# Koala_Bear.net
KiCad netlist of a schematic drawn in EAGLE
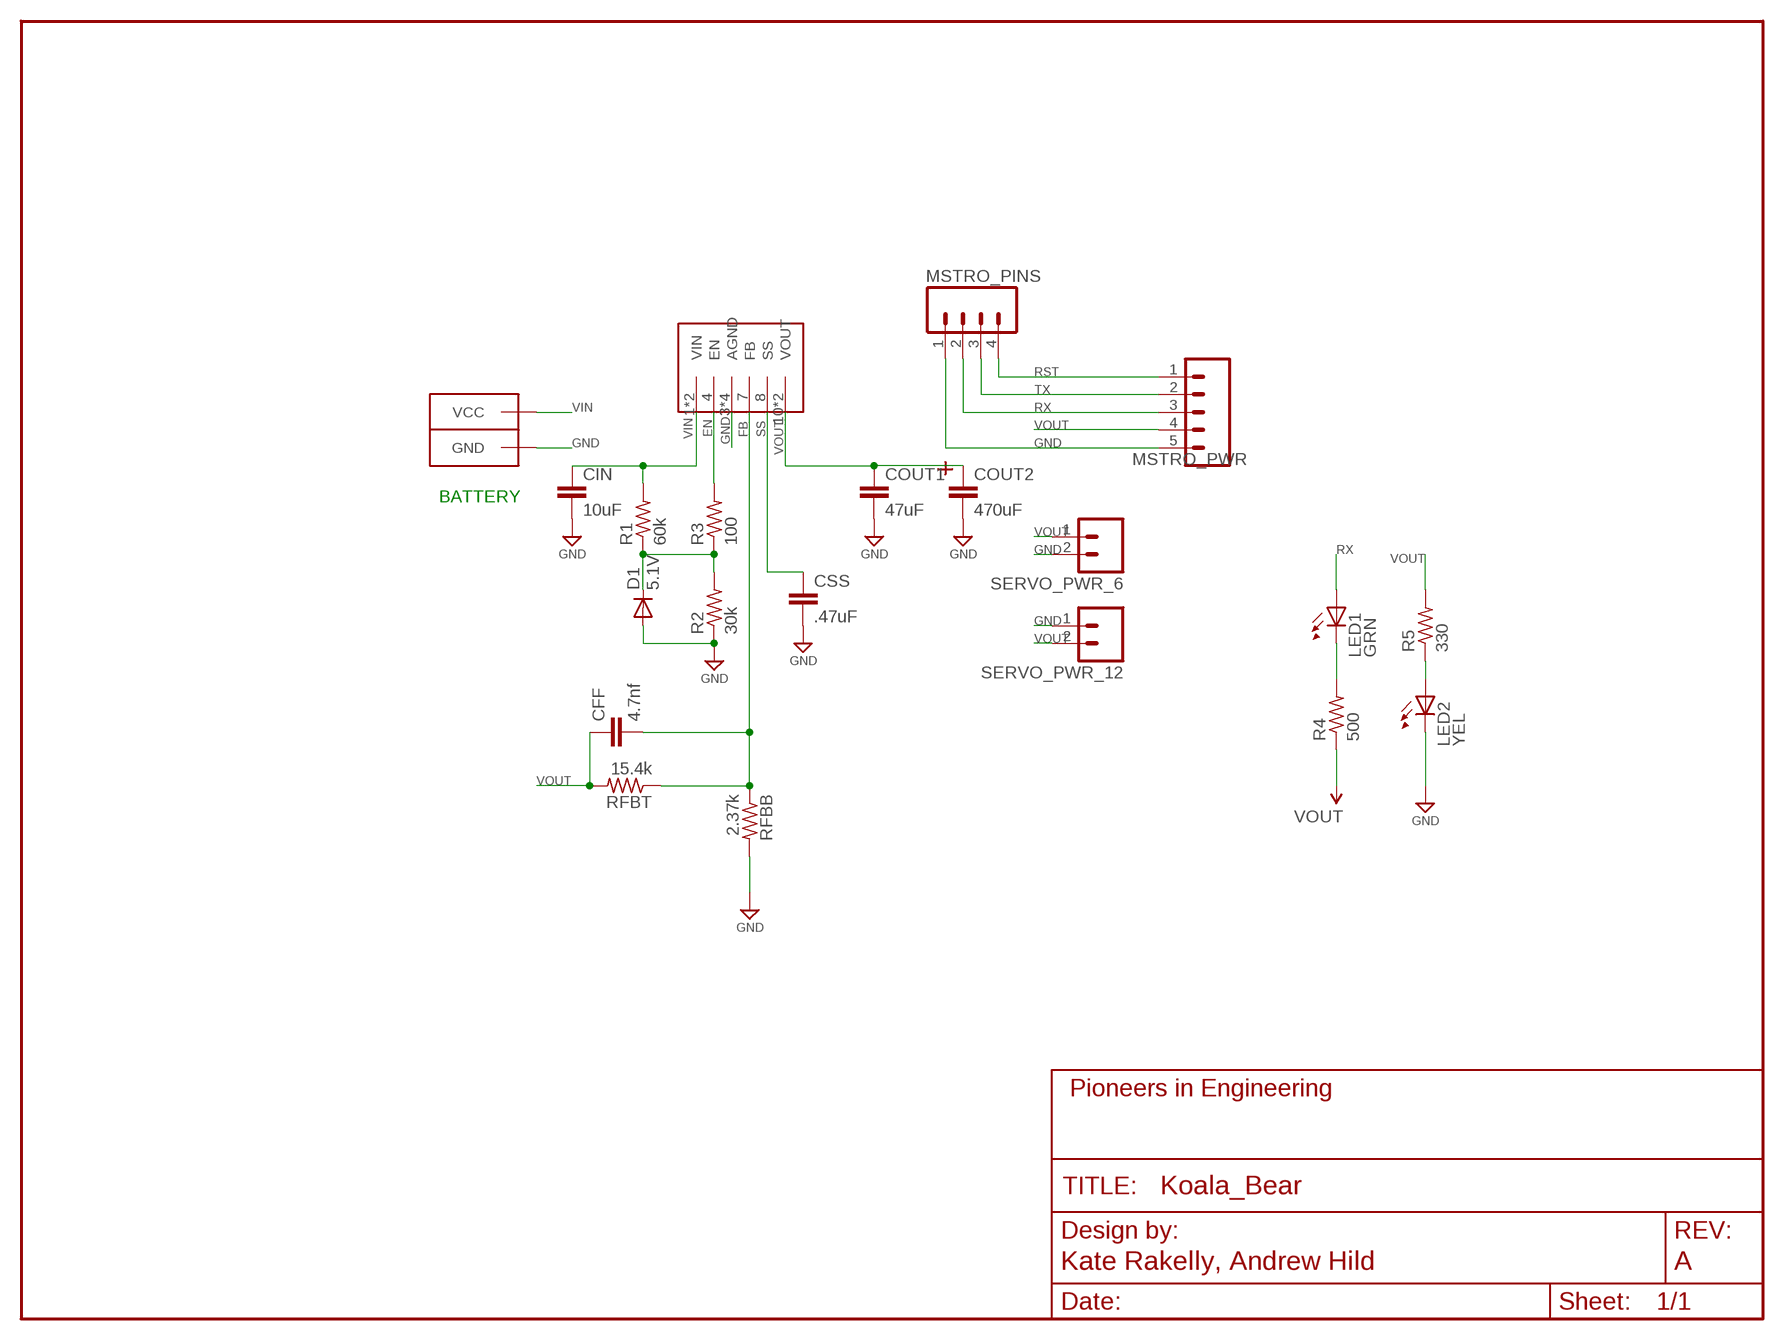
[diagram p0: schematic, sheet 1]

(export (version "E")
  (design (tool "Eeschema 10.0.6"))
  (components
    (comp (ref "CFF")
      (value "4.7nf")
      (footprint "eagle-import:0603-CAP")
      (libsource (lib "eagle-import") (part "pie_CAP0603-CAP"))
    )
    (comp (ref "CIN")
      (value "10uF")
      (footprint "eagle-import:0603-CAP")
      (libsource (lib "eagle-import") (part "pie_CAP0603-CAP"))
    )
    (comp (ref "COUT1")
      (value "47uF")
      (footprint "eagle-import:1206")
      (libsource (lib "eagle-import") (part "CAP1206"))
    )
    (comp (ref "COUT2")
      (value "470uF")
      (footprint "eagle-import:TANT_CASE_E")
      (libsource (lib "eagle-import") (part "TANT_CASE_E"))
    )
    (comp (ref "CSS")
      (value ".47uF")
      (footprint "eagle-import:0603-CAP")
      (libsource (lib "eagle-import") (part "pie_CAP0603-CAP"))
    )
    (comp (ref "D1")
      (value "5.1V")
      (footprint "eagle-import:SOD-323")
      (libsource (lib "eagle-import") (part "DIODESOD"))
    )
    (comp (ref "LED1")
      (value "GRN")
      (footprint "eagle-import:LED-0805")
      (libsource (lib "eagle-import") (part "LED0805"))
    )
    (comp (ref "LED2")
      (value "YEL")
      (footprint "eagle-import:LED-0805")
      (libsource (lib "eagle-import") (part "LED0805"))
    )
    (comp (ref "MSTRO_PINS")
      (value "M041X04-MTA")
      (footprint "eagle-import:1X04-MTA")
      (fields (field (name "PARTNUMBER") "A1922-ND"))
      (libsource (lib "eagle-import") (part "M041X04-MTA"))
    )
    (comp (ref "MSTRO_PWR")
      (value "M05MTA")
      (footprint "eagle-import:1X05-MTA")
      (fields (field (name "PARTNUMBER") "A19471-ND"))
      (libsource (lib "eagle-import") (part "M05MTA"))
    )
    (comp (ref "PWR")
      (value "ANDERSONVERTICAL")
      (footprint "eagle-import:ANDERSON_VERTICAL")
      (fields (field (name "PARTNUMBER") "1377G3"))
      (libsource (lib "eagle-import") (part "ANDERSONVERTICAL"))
    )
    (comp (ref "R1")
      (value "60k")
      (footprint "eagle-import:R0603")
      (libsource (lib "eagle-import") (part "R-US_R0603"))
    )
    (comp (ref "R2")
      (value "30k")
      (footprint "eagle-import:R0603")
      (libsource (lib "eagle-import") (part "R-US_R0603"))
    )
    (comp (ref "R3")
      (value "100")
      (footprint "eagle-import:R0603")
      (libsource (lib "eagle-import") (part "R-US_R0603"))
    )
    (comp (ref "R4")
      (value "500")
      (footprint "eagle-import:R0603")
      (libsource (lib "eagle-import") (part "R-US_R0603"))
    )
    (comp (ref "R5")
      (value "330")
      (footprint "eagle-import:R0603")
      (libsource (lib "eagle-import") (part "R-US_R0603"))
    )
    (comp (ref "RFBB")
      (value "2.37k")
      (footprint "eagle-import:R0603")
      (libsource (lib "eagle-import") (part "R-US_R0603"))
    )
    (comp (ref "RFBT")
      (value "15.4k")
      (footprint "eagle-import:R0603")
      (libsource (lib "eagle-import") (part "R-US_R0603"))
    )
    (comp (ref "SERVO_PWR_6")
      (value "M02PTH")
      (footprint "eagle-import:1X02")
      (libsource (lib "eagle-import") (part "M02PTH"))
    )
    (comp (ref "SERVO_PWR_12")
      (value "M02PTH")
      (footprint "eagle-import:1X02")
      (libsource (lib "eagle-import") (part "M02PTH"))
    )
    (comp (ref "U$1")
      (value "LMZ12010")
      (footprint "eagle-import:LMZ12010")
      (libsource (lib "eagle-import") (part "LMZ12010"))
    )
  )
  (nets
    (net (code "1") (name "/EN") (class "Default")
      (node (ref "R3") (pin "2") (pinfunction "2_2") (pintype "passive"))
      (node (ref "U$1") (pin "4") (pinfunction "EN_4") (pintype "bidirectional"))
    )
    (net (code "2") (name "/FB") (class "Default")
      (node (ref "CFF") (pin "2") (pinfunction "2_2") (pintype "passive"))
      (node (ref "RFBB") (pin "1") (pinfunction "1_1") (pintype "passive"))
      (node (ref "RFBT") (pin "1") (pinfunction "1_1") (pintype "passive"))
      (node (ref "U$1") (pin "7") (pinfunction "FB_7") (pintype "bidirectional"))
    )
    (net (code "3") (name "/RST") (class "Default")
      (node (ref "MSTRO_PINS") (pin "4") (pinfunction "4_4") (pintype "passive"))
      (node (ref "MSTRO_PWR") (pin "1") (pinfunction "1_1") (pintype "passive"))
    )
    (net (code "4") (name "/RX") (class "Default")
      (node (ref "LED1") (pin "A") (pinfunction "A_A") (pintype "passive"))
      (node (ref "MSTRO_PINS") (pin "2") (pinfunction "2_2") (pintype "passive"))
      (node (ref "MSTRO_PWR") (pin "3") (pinfunction "3_3") (pintype "passive"))
    )
    (net (code "5") (name "/SS") (class "Default")
      (node (ref "CSS") (pin "1") (pinfunction "1_1") (pintype "passive"))
      (node (ref "U$1") (pin "8") (pinfunction "SS_8") (pintype "bidirectional"))
    )
    (net (code "6") (name "/TX") (class "Default")
      (node (ref "MSTRO_PINS") (pin "3") (pinfunction "3_3") (pintype "passive"))
      (node (ref "MSTRO_PWR") (pin "2") (pinfunction "2_2") (pintype "passive"))
    )
    (net (code "7") (name "/VIN") (class "Default")
      (node (ref "CIN") (pin "1") (pinfunction "1_1") (pintype "passive"))
      (node (ref "PWR") (pin "PIN2") (pinfunction "VCC_PIN2") (pintype "bidirectional"))
      (node (ref "R1") (pin "2") (pinfunction "2_2") (pintype "passive"))
      (node (ref "U$1") (pin "1") (pinfunction "VIN_1") (pintype "bidirectional"))
      (node (ref "U$1") (pin "2") (pinfunction "VIN_2") (pintype "bidirectional"))
    )
    (net (code "8") (name "GND") (class "Default")
      (node (ref "CIN") (pin "2") (pinfunction "2_2") (pintype "passive"))
      (node (ref "COUT1") (pin "2") (pinfunction "2_2") (pintype "passive"))
      (node (ref "COUT2") (pin "NEG") (pinfunction "NEG_NEG") (pintype "passive"))
      (node (ref "CSS") (pin "2") (pinfunction "2_2") (pintype "passive"))
      (node (ref "D1") (pin "2") (pinfunction "A_2") (pintype "passive"))
      (node (ref "LED2") (pin "C") (pinfunction "C_C") (pintype "passive"))
      (node (ref "MSTRO_PINS") (pin "1") (pinfunction "1_1") (pintype "passive"))
      (node (ref "MSTRO_PWR") (pin "5") (pinfunction "5_5") (pintype "passive"))
      (node (ref "PWR") (pin "PIN1") (pinfunction "GND_PIN1") (pintype "bidirectional"))
      (node (ref "R2") (pin "1") (pinfunction "1_1") (pintype "passive"))
      (node (ref "RFBB") (pin "2") (pinfunction "2_2") (pintype "passive"))
      (node (ref "SERVO_PWR_12") (pin "1") (pinfunction "1_1") (pintype "passive"))
      (node (ref "SERVO_PWR_6") (pin "2") (pinfunction "2_2") (pintype "passive"))
      (node (ref "U$1") (pin "3") (pinfunction "AGND_3") (pintype "bidirectional"))
      (node (ref "U$1") (pin "5") (pinfunction "AGND_5") (pintype "bidirectional"))
      (node (ref "U$1") (pin "6") (pinfunction "AGND_6") (pintype "bidirectional"))
      (node (ref "U$1") (pin "GND") (pinfunction "AGND_GND") (pintype "bidirectional"))
    )
    (net (code "9") (name "Net-(D1-C)") (class "Default")
      (node (ref "D1") (pin "1") (pinfunction "C_1") (pintype "passive"))
      (node (ref "R1") (pin "1") (pinfunction "1_1") (pintype "passive"))
      (node (ref "R2") (pin "2") (pinfunction "2_2") (pintype "passive"))
      (node (ref "R3") (pin "1") (pinfunction "1_1") (pintype "passive"))
    )
    (net (code "10") (name "Net-(LED1-PadC)") (class "Default")
      (node (ref "LED1") (pin "C") (pinfunction "C_C") (pintype "passive"))
      (node (ref "R4") (pin "2") (pinfunction "2_2") (pintype "passive"))
    )
    (net (code "11") (name "Net-(LED2-PadA)") (class "Default")
      (node (ref "LED2") (pin "A") (pinfunction "A_A") (pintype "passive"))
      (node (ref "R5") (pin "1") (pinfunction "1_1") (pintype "passive"))
    )
    (net (code "12") (name "VOUT") (class "Default")
      (node (ref "CFF") (pin "1") (pinfunction "1_1") (pintype "passive"))
      (node (ref "COUT1") (pin "1") (pinfunction "1_1") (pintype "passive"))
      (node (ref "COUT2") (pin "POS") (pinfunction "POS_POS") (pintype "passive"))
      (node (ref "MSTRO_PWR") (pin "4") (pinfunction "4_4") (pintype "passive"))
      (node (ref "R4") (pin "1") (pinfunction "1_1") (pintype "passive"))
      (node (ref "R5") (pin "2") (pinfunction "2_2") (pintype "passive"))
      (node (ref "RFBT") (pin "2") (pinfunction "2_2") (pintype "passive"))
      (node (ref "SERVO_PWR_12") (pin "2") (pinfunction "2_2") (pintype "passive"))
      (node (ref "SERVO_PWR_6") (pin "1") (pinfunction "1_1") (pintype "passive"))
      (node (ref "U$1") (pin "10") (pinfunction "VOUT_10") (pintype "bidirectional"))
      (node (ref "U$1") (pin "11") (pinfunction "VOUT_11") (pintype "bidirectional"))
    )
  )
)
